# esquematico.net
KiCad netlist of a schematic drawn in Altium Designer
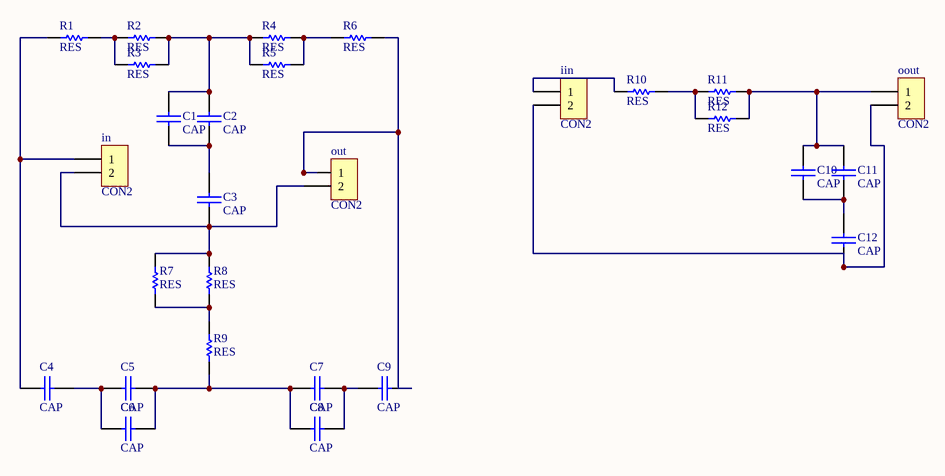
[diagram p0: esquematico.SchDoc]

(export (version "E")
  (design (tool "Eeschema 10.0.6"))
  (components
    (comp (ref "C1") (value "CAP") (footprint "CAP200") (libsource (lib "LIBEBAL") (part "CAP")))
    (comp (ref "C2") (value "CAP") (footprint "CAP200") (libsource (lib "LIBEBAL") (part "CAP")))
    (comp (ref "C3") (value "CAP") (footprint "CAP200") (libsource (lib "LIBEBAL") (part "CAP")))
    (comp (ref "C4") (value "CAP") (footprint "CAP200") (libsource (lib "LIBEBAL") (part "CAP")))
    (comp (ref "C5") (value "CAP") (footprint "CAP200") (libsource (lib "LIBEBAL") (part "CAP")))
    (comp (ref "C6") (value "CAP") (footprint "CAP200") (libsource (lib "LIBEBAL") (part "CAP")))
    (comp (ref "C7") (value "CAP") (footprint "CAP200") (libsource (lib "LIBEBAL") (part "CAP")))
    (comp (ref "C8") (value "CAP") (footprint "CAP200") (libsource (lib "LIBEBAL") (part "CAP")))
    (comp (ref "C9") (value "CAP") (footprint "CAP200") (libsource (lib "LIBEBAL") (part "CAP")))
    (comp (ref "C10") (value "CAP") (footprint "CAP200") (libsource (lib "LIBEBAL") (part "CAP")))
    (comp (ref "C11") (value "CAP") (footprint "CAP200") (libsource (lib "LIBEBAL") (part "CAP")))
    (comp (ref "C12") (value "CAP") (footprint "CAP200") (libsource (lib "LIBEBAL") (part "CAP")))
    (comp (ref "iin") (value "CON2") (footprint "SIP2") (libsource (lib "LIBEBAL") (part "CON2")))
    (comp (ref "in") (value "CON2") (footprint "SIP2") (libsource (lib "LIBEBAL") (part "CON2")))
    (comp (ref "oout") (value "CON2") (footprint "SIP2") (libsource (lib "LIBEBAL") (part "CON2")))
    (comp (ref "out") (value "CON2") (footprint "SIP2") (libsource (lib "LIBEBAL") (part "CON2")))
    (comp (ref "R1") (value "RES") (footprint "RES400") (libsource (lib "LIBEBAL") (part "RES")))
    (comp (ref "R2") (value "RES") (footprint "RES400") (libsource (lib "LIBEBAL") (part "RES")))
    (comp (ref "R3") (value "RES") (footprint "RES400") (libsource (lib "LIBEBAL") (part "RES")))
    (comp (ref "R4") (value "RES") (footprint "RES400") (libsource (lib "LIBEBAL") (part "RES")))
    (comp (ref "R5") (value "RES") (footprint "RES400") (libsource (lib "LIBEBAL") (part "RES")))
    (comp (ref "R6") (value "RES") (footprint "RES400") (libsource (lib "LIBEBAL") (part "RES")))
    (comp (ref "R7") (value "RES") (footprint "RES400") (libsource (lib "LIBEBAL") (part "RES")))
    (comp (ref "R8") (value "RES") (footprint "RES400") (libsource (lib "LIBEBAL") (part "RES")))
    (comp (ref "R9") (value "RES") (footprint "RES400") (libsource (lib "LIBEBAL") (part "RES")))
    (comp (ref "R10") (value "RES") (footprint "RES400") (libsource (lib "LIBEBAL") (part "RES")))
    (comp (ref "R11") (value "RES") (footprint "RES400") (libsource (lib "LIBEBAL") (part "RES")))
    (comp (ref "R12") (value "RES") (footprint "RES400") (libsource (lib "LIBEBAL") (part "RES")))
  )
  (nets
    (net (code "1") (name "Net-(C1-Pad1)") (class "Default")
      (node (ref "C1") (pin "1") (pinfunction "1_1") (pintype "passive"))
      (node (ref "C2") (pin "1") (pinfunction "1_1") (pintype "passive"))
      (node (ref "R2") (pin "2") (pinfunction "2_2") (pintype "passive"))
      (node (ref "R3") (pin "2") (pinfunction "2_2") (pintype "passive"))
      (node (ref "R4") (pin "1") (pinfunction "1_1") (pintype "passive"))
      (node (ref "R5") (pin "1") (pinfunction "1_1") (pintype "passive"))
    )
    (net (code "2") (name "Net-(C1-Pad2)") (class "Default")
      (node (ref "C1") (pin "2") (pinfunction "2_2") (pintype "passive"))
      (node (ref "C2") (pin "2") (pinfunction "2_2") (pintype "passive"))
      (node (ref "C3") (pin "1") (pinfunction "1_1") (pintype "passive"))
    )
    (net (code "3") (name "Net-(C3-Pad2)") (class "Default")
      (node (ref "C3") (pin "2") (pinfunction "2_2") (pintype "passive"))
      (node (ref "R7") (pin "2") (pinfunction "2_2") (pintype "passive"))
      (node (ref "R8") (pin "2") (pinfunction "2_2") (pintype "passive"))
      (node (ref "in") (pin "2") (pinfunction "2_2") (pintype "passive"))
      (node (ref "out") (pin "2") (pinfunction "2_2") (pintype "passive"))
    )
    (net (code "4") (name "Net-(C4-Pad1)") (class "Default")
      (node (ref "C4") (pin "1") (pinfunction "1_1") (pintype "passive"))
      (node (ref "R1") (pin "1") (pinfunction "1_1") (pintype "passive"))
      (node (ref "in") (pin "1") (pinfunction "1_1") (pintype "passive"))
    )
    (net (code "5") (name "Net-(C4-Pad2)") (class "Default")
      (node (ref "C4") (pin "2") (pinfunction "2_2") (pintype "passive"))
      (node (ref "C5") (pin "1") (pinfunction "1_1") (pintype "passive"))
      (node (ref "C6") (pin "1") (pinfunction "1_1") (pintype "passive"))
    )
    (net (code "6") (name "Net-(C5-Pad2)") (class "Default")
      (node (ref "C5") (pin "2") (pinfunction "2_2") (pintype "passive"))
      (node (ref "C6") (pin "2") (pinfunction "2_2") (pintype "passive"))
      (node (ref "C7") (pin "2") (pinfunction "2_2") (pintype "passive"))
      (node (ref "C8") (pin "1") (pinfunction "1_1") (pintype "passive"))
      (node (ref "R9") (pin "1") (pinfunction "1_1") (pintype "passive"))
    )
    (net (code "7") (name "Net-(C7-Pad1)") (class "Default")
      (node (ref "C7") (pin "1") (pinfunction "1_1") (pintype "passive"))
      (node (ref "C8") (pin "2") (pinfunction "2_2") (pintype "passive"))
      (node (ref "C9") (pin "1") (pinfunction "1_1") (pintype "passive"))
    )
    (net (code "8") (name "Net-(C9-Pad2)") (class "Default")
      (node (ref "C9") (pin "2") (pinfunction "2_2") (pintype "passive"))
      (node (ref "R6") (pin "2") (pinfunction "2_2") (pintype "passive"))
      (node (ref "out") (pin "1") (pinfunction "1_1") (pintype "passive"))
    )
    (net (code "9") (name "Net-(C10-Pad1)") (class "Default")
      (node (ref "C10") (pin "1") (pinfunction "1_1") (pintype "passive"))
      (node (ref "C11") (pin "1") (pinfunction "1_1") (pintype "passive"))
      (node (ref "R11") (pin "2") (pinfunction "2_2") (pintype "passive"))
      (node (ref "R12") (pin "2") (pinfunction "2_2") (pintype "passive"))
      (node (ref "oout") (pin "1") (pinfunction "1_1") (pintype "passive"))
    )
    (net (code "10") (name "Net-(C10-Pad2)") (class "Default")
      (node (ref "C10") (pin "2") (pinfunction "2_2") (pintype "passive"))
      (node (ref "C11") (pin "2") (pinfunction "2_2") (pintype "passive"))
      (node (ref "C12") (pin "1") (pinfunction "1_1") (pintype "passive"))
    )
    (net (code "11") (name "Net-(C12-Pad2)") (class "Default")
      (node (ref "C12") (pin "2") (pinfunction "2_2") (pintype "passive"))
      (node (ref "iin") (pin "2") (pinfunction "2_2") (pintype "passive"))
      (node (ref "oout") (pin "2") (pinfunction "2_2") (pintype "passive"))
    )
    (net (code "12") (name "Net-(R1-Pad2)") (class "Default")
      (node (ref "R1") (pin "2") (pinfunction "2_2") (pintype "passive"))
      (node (ref "R2") (pin "1") (pinfunction "1_1") (pintype "passive"))
      (node (ref "R3") (pin "1") (pinfunction "1_1") (pintype "passive"))
    )
    (net (code "13") (name "Net-(R4-Pad2)") (class "Default")
      (node (ref "R4") (pin "2") (pinfunction "2_2") (pintype "passive"))
      (node (ref "R5") (pin "2") (pinfunction "2_2") (pintype "passive"))
      (node (ref "R6") (pin "1") (pinfunction "1_1") (pintype "passive"))
    )
    (net (code "14") (name "Net-(R7-Pad1)") (class "Default")
      (node (ref "R7") (pin "1") (pinfunction "1_1") (pintype "passive"))
      (node (ref "R8") (pin "1") (pinfunction "1_1") (pintype "passive"))
      (node (ref "R9") (pin "2") (pinfunction "2_2") (pintype "passive"))
    )
    (net (code "15") (name "Net-(R10-Pad1)") (class "Default")
      (node (ref "R10") (pin "1") (pinfunction "1_1") (pintype "passive"))
      (node (ref "iin") (pin "1") (pinfunction "1_1") (pintype "passive"))
    )
    (net (code "16") (name "Net-(R10-Pad2)") (class "Default")
      (node (ref "R10") (pin "2") (pinfunction "2_2") (pintype "passive"))
      (node (ref "R11") (pin "1") (pinfunction "1_1") (pintype "passive"))
      (node (ref "R12") (pin "1") (pinfunction "1_1") (pintype "passive"))
    )
  )
)
